# sx1509-breakout_mount_remap2.net
KiCad netlist of a schematic drawn in EAGLE
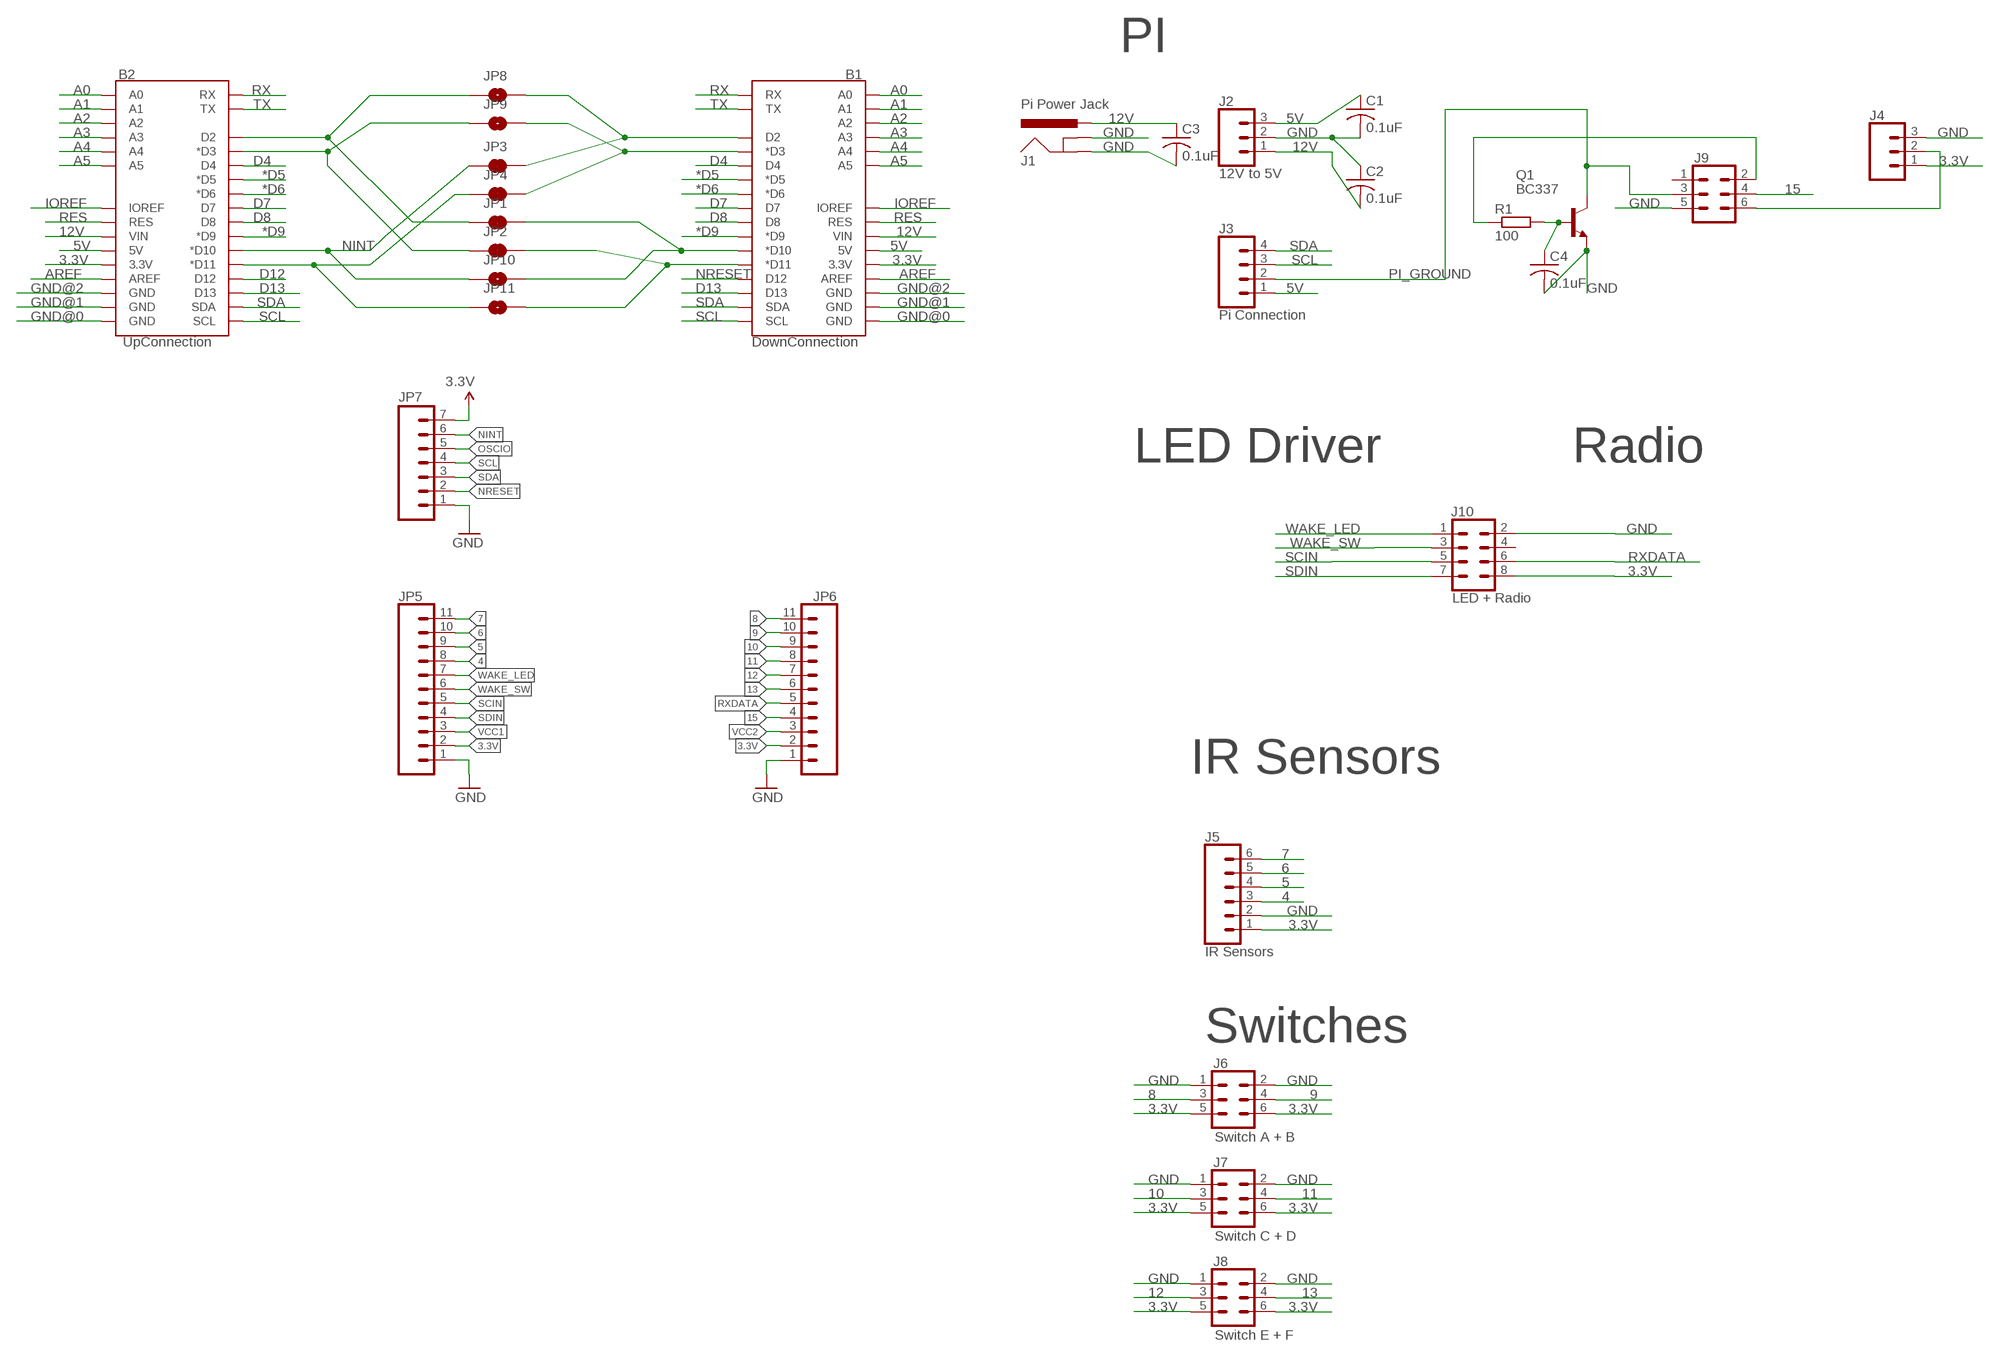
[diagram p0: schematic, sheet 1]

(export (version "E")
  (design (tool "Eeschema 10.0.6"))
  (components
    (comp (ref "B1")
      (value "DownConnection")
      (footprint "eagle-import:UNO_R3_SHIELD_NOLABELS")
      (libsource (lib "eagle-import") (part "ARDUINO_UNO_R3_SHIELDNOLABELS"))
    )
    (comp (ref "B2")
      (value "UpConnection")
      (footprint "eagle-import:UNO_R3_SHIELD_NOLABELS")
      (libsource (lib "eagle-import") (part "ARDUINO_UNO_R3_SHIELDNOLABELS"))
    )
    (comp (ref "C1")
      (value "0.1uF")
      (footprint "eagle-import:C025-024X044")
      (libsource (lib "eagle-import") (part "C-US025-024X044"))
    )
    (comp (ref "C2")
      (value "0.1uF")
      (footprint "eagle-import:C025-024X044")
      (libsource (lib "eagle-import") (part "C-US025-024X044"))
    )
    (comp (ref "C3")
      (value "0.1uF")
      (footprint "eagle-import:C025-024X044")
      (libsource (lib "eagle-import") (part "C-US025-024X044"))
    )
    (comp (ref "C4")
      (value "0.1uF")
      (footprint "eagle-import:C025-024X044")
      (libsource (lib "eagle-import") (part "C-US025-024X044"))
    )
    (comp (ref "J1")
      (value "Pi Power Jack")
      (footprint "eagle-import:POWER_JACK_PTH_BREAD")
      (libsource (lib "eagle-import") (part "POWER_JACKPTH_BREAD"))
    )
    (comp (ref "J2")
      (value "12V to 5V")
      (footprint "eagle-import:1X03")
      (libsource (lib "eagle-import") (part "CONN_03"))
    )
    (comp (ref "J3")
      (value "Pi Connection")
      (footprint "eagle-import:1X04")
      (libsource (lib "eagle-import") (part "CONN_04"))
    )
    (comp (ref "J4")
      (value "CONN_03")
      (footprint "eagle-import:1X03")
      (libsource (lib "eagle-import") (part "CONN_03"))
    )
    (comp (ref "J5")
      (value "IR Sensors")
      (footprint "eagle-import:1X06")
      (libsource (lib "eagle-import") (part "CONN_06SILK_FEMALE_PTH"))
    )
    (comp (ref "J6")
      (value "Switch A + B")
      (footprint "eagle-import:2X3")
      (libsource (lib "eagle-import") (part "CONN_03X2FEMALE"))
    )
    (comp (ref "J7")
      (value "Switch C + D")
      (footprint "eagle-import:2X3")
      (libsource (lib "eagle-import") (part "CONN_03X2FEMALE"))
    )
    (comp (ref "J8")
      (value "Switch E + F")
      (footprint "eagle-import:2X3")
      (libsource (lib "eagle-import") (part "CONN_03X2FEMALE"))
    )
    (comp (ref "J9")
      (value "CONN_03X2NO_SILK")
      (footprint "eagle-import:2X3-NS")
      (libsource (lib "eagle-import") (part "CONN_03X2NO_SILK"))
    )
    (comp (ref "J10")
      (value "LED + Radio")
      (footprint "eagle-import:2X4")
      (libsource (lib "eagle-import") (part "CONN_04X2"))
    )
    (comp (ref "JP1")
      (value "JUMPER-SMT_2_NC_TRACE_NO-SILK")
      (footprint "eagle-import:SMT-JUMPER_2_NC_TRACE_NO-SILK")
      (libsource (lib "eagle-import") (part "JUMPER-SMT_2_NC_TRACE_NO-SILK"))
    )
    (comp (ref "JP2")
      (value "JUMPER-SMT_2_NC_TRACE_NO-SILK")
      (footprint "eagle-import:SMT-JUMPER_2_NC_TRACE_NO-SILK")
      (libsource (lib "eagle-import") (part "JUMPER-SMT_2_NC_TRACE_NO-SILK"))
    )
    (comp (ref "JP3")
      (value "JUMPER-SMT_2_NC_TRACE_NO-SILK")
      (footprint "eagle-import:SMT-JUMPER_2_NC_TRACE_NO-SILK")
      (libsource (lib "eagle-import") (part "JUMPER-SMT_2_NC_TRACE_NO-SILK"))
    )
    (comp (ref "JP4")
      (value "JUMPER-SMT_2_NC_TRACE_NO-SILK")
      (footprint "eagle-import:SMT-JUMPER_2_NC_TRACE_NO-SILK")
      (libsource (lib "eagle-import") (part "JUMPER-SMT_2_NC_TRACE_NO-SILK"))
    )
    (comp (ref "JP5")
      (value "CONN_11")
      (footprint "eagle-import:1X11")
      (libsource (lib "eagle-import") (part "CONN_11"))
    )
    (comp (ref "JP6")
      (value "CONN_11")
      (footprint "eagle-import:1X11")
      (libsource (lib "eagle-import") (part "CONN_11"))
    )
    (comp (ref "JP7")
      (value "M07")
      (footprint "eagle-import:1X07")
      (libsource (lib "eagle-import") (part "M07"))
    )
    (comp (ref "JP8")
      (value "JUMPER-SMT_2_NO_NO-SILK")
      (footprint "eagle-import:SMT-JUMPER_2_NO_NO-SILK")
      (libsource (lib "eagle-import") (part "JUMPER-SMT_2_NO_NO-SILK"))
    )
    (comp (ref "JP9")
      (value "JUMPER-SMT_2_NO_NO-SILK")
      (footprint "eagle-import:SMT-JUMPER_2_NO_NO-SILK")
      (libsource (lib "eagle-import") (part "JUMPER-SMT_2_NO_NO-SILK"))
    )
    (comp (ref "JP10")
      (value "JUMPER-SMT_2_NO_NO-SILK")
      (footprint "eagle-import:SMT-JUMPER_2_NO_NO-SILK")
      (libsource (lib "eagle-import") (part "JUMPER-SMT_2_NO_NO-SILK"))
    )
    (comp (ref "JP11")
      (value "JUMPER-SMT_2_NO_NO-SILK")
      (footprint "eagle-import:SMT-JUMPER_2_NO_NO-SILK")
      (libsource (lib "eagle-import") (part "JUMPER-SMT_2_NO_NO-SILK"))
    )
    (comp (ref "Q1")
      (value "BC337")
      (footprint "eagle-import:TO92")
      (libsource (lib "eagle-import") (part "BC337"))
    )
    (comp (ref "R1")
      (value "100")
      (footprint "eagle-import:0204_7")
      (libsource (lib "eagle-import") (part "R0204/7"))
    )
  )
  (nets
    (net (code "1") (name "/*D5") (class "Default")
      (node (ref "B1") (pin "D5") (pinfunction "*D5_D5") (pintype "bidirectional"))
      (node (ref "B2") (pin "D5") (pinfunction "*D5_D5") (pintype "bidirectional"))
    )
    (net (code "2") (name "/*D6") (class "Default")
      (node (ref "B1") (pin "D6") (pinfunction "*D6_D6") (pintype "bidirectional"))
      (node (ref "B2") (pin "D6") (pinfunction "*D6_D6") (pintype "bidirectional"))
    )
    (net (code "3") (name "/*D9") (class "Default")
      (node (ref "B1") (pin "D9") (pinfunction "*D9_D9") (pintype "bidirectional"))
      (node (ref "B2") (pin "D9") (pinfunction "*D9_D9") (pintype "bidirectional"))
    )
    (net (code "4") (name "/5V") (class "Default")
      (node (ref "B1") (pin "5V") (pinfunction "5V_5V") (pintype "bidirectional"))
      (node (ref "B2") (pin "5V") (pinfunction "5V_5V") (pintype "bidirectional"))
      (node (ref "C1") (pin "1") (pinfunction "1_1") (pintype "passive"))
      (node (ref "J2") (pin "3") (pinfunction "3_3") (pintype "passive"))
      (node (ref "J3") (pin "1") (pinfunction "1_1") (pintype "passive"))
    )
    (net (code "5") (name "/12V") (class "Default")
      (node (ref "B1") (pin "VIN") (pinfunction "VIN_VIN") (pintype "bidirectional"))
      (node (ref "B2") (pin "VIN") (pinfunction "VIN_VIN") (pintype "bidirectional"))
      (node (ref "C2") (pin "2") (pinfunction "2_2") (pintype "passive"))
      (node (ref "C3") (pin "1") (pinfunction "1_1") (pintype "passive"))
      (node (ref "J1") (pin "PWR") (pinfunction "PWR_PWR") (pintype "bidirectional"))
      (node (ref "J2") (pin "1") (pinfunction "1_1") (pintype "passive"))
    )
    (net (code "6") (name "/A0") (class "Default")
      (node (ref "B1") (pin "A0") (pinfunction "A0_A0") (pintype "bidirectional"))
      (node (ref "B2") (pin "A0") (pinfunction "A0_A0") (pintype "bidirectional"))
    )
    (net (code "7") (name "/A1") (class "Default")
      (node (ref "B1") (pin "A1") (pinfunction "A1_A1") (pintype "bidirectional"))
      (node (ref "B2") (pin "A1") (pinfunction "A1_A1") (pintype "bidirectional"))
    )
    (net (code "8") (name "/A2") (class "Default")
      (node (ref "B1") (pin "A2") (pinfunction "A2_A2") (pintype "bidirectional"))
      (node (ref "B2") (pin "A2") (pinfunction "A2_A2") (pintype "bidirectional"))
    )
    (net (code "9") (name "/A3") (class "Default")
      (node (ref "B1") (pin "A3") (pinfunction "A3_A3") (pintype "bidirectional"))
      (node (ref "B2") (pin "A3") (pinfunction "A3_A3") (pintype "bidirectional"))
    )
    (net (code "10") (name "/A4") (class "Default")
      (node (ref "B1") (pin "A4") (pinfunction "A4_A4") (pintype "bidirectional"))
      (node (ref "B2") (pin "A4") (pinfunction "A4_A4") (pintype "bidirectional"))
    )
    (net (code "11") (name "/A5") (class "Default")
      (node (ref "B1") (pin "A5") (pinfunction "A5_A5") (pintype "bidirectional"))
      (node (ref "B2") (pin "A5") (pinfunction "A5_A5") (pintype "bidirectional"))
    )
    (net (code "12") (name "/AREF") (class "Default")
      (node (ref "B1") (pin "AREF") (pinfunction "AREF_AREF") (pintype "bidirectional"))
      (node (ref "B2") (pin "AREF") (pinfunction "AREF_AREF") (pintype "bidirectional"))
    )
    (net (code "13") (name "/D4") (class "Default")
      (node (ref "B1") (pin "D4") (pinfunction "D4_D4") (pintype "bidirectional"))
      (node (ref "B2") (pin "D4") (pinfunction "D4_D4") (pintype "bidirectional"))
    )
    (net (code "14") (name "/D7") (class "Default")
      (node (ref "B1") (pin "D7") (pinfunction "D7_D7") (pintype "bidirectional"))
      (node (ref "B2") (pin "D7") (pinfunction "D7_D7") (pintype "bidirectional"))
    )
    (net (code "15") (name "/D8") (class "Default")
      (node (ref "B1") (pin "D8") (pinfunction "D8_D8") (pintype "bidirectional"))
      (node (ref "B2") (pin "D8") (pinfunction "D8_D8") (pintype "bidirectional"))
    )
    (net (code "16") (name "/D12") (class "Default")
      (node (ref "B2") (pin "D12") (pinfunction "D12_D12") (pintype "bidirectional"))
    )
    (net (code "17") (name "/D13") (class "Default")
      (node (ref "B1") (pin "D13") (pinfunction "D13_D13") (pintype "bidirectional"))
      (node (ref "B2") (pin "D13") (pinfunction "D13_D13") (pintype "bidirectional"))
    )
    (net (code "18") (name "/GND@0") (class "Default")
      (node (ref "B1") (pin "GND@0") (pinfunction "GND_GND@0") (pintype "bidirectional"))
      (node (ref "B2") (pin "GND@0") (pinfunction "GND_GND@0") (pintype "bidirectional"))
    )
    (net (code "19") (name "/GND@1") (class "Default")
      (node (ref "B1") (pin "GND@1") (pinfunction "GND_GND@1") (pintype "bidirectional"))
      (node (ref "B2") (pin "GND@1") (pinfunction "GND_GND@1") (pintype "bidirectional"))
    )
    (net (code "20") (name "/GND@2") (class "Default")
      (node (ref "B1") (pin "GND@2") (pinfunction "GND_GND@2") (pintype "bidirectional"))
      (node (ref "B2") (pin "GND@2") (pinfunction "GND_GND@2") (pintype "bidirectional"))
    )
    (net (code "21") (name "/IOREF") (class "Default")
      (node (ref "B1") (pin "IOREF") (pinfunction "IOREF_IOREF") (pintype "bidirectional"))
      (node (ref "B2") (pin "IOREF") (pinfunction "IOREF_IOREF") (pintype "bidirectional"))
    )
    (net (code "22") (name "/PI_GROUND") (class "Default")
      (node (ref "J3") (pin "2") (pinfunction "2_2") (pintype "passive"))
      (node (ref "J9") (pin "3") (pinfunction "3_3") (pintype "bidirectional"))
      (node (ref "Q1") (pin "3") (pinfunction "C_3") (pintype "passive"))
    )
    (net (code "23") (name "/RES") (class "Default")
      (node (ref "B1") (pin "RES") (pinfunction "RES_RES") (pintype "bidirectional"))
      (node (ref "B2") (pin "RES") (pinfunction "RES_RES") (pintype "bidirectional"))
    )
    (net (code "24") (name "/RX") (class "Default")
      (node (ref "B1") (pin "RX") (pinfunction "RX_RX") (pintype "bidirectional"))
      (node (ref "B2") (pin "RX") (pinfunction "RX_RX") (pintype "bidirectional"))
    )
    (net (code "25") (name "/TX") (class "Default")
      (node (ref "B1") (pin "TX") (pinfunction "TX_TX") (pintype "bidirectional"))
      (node (ref "B2") (pin "TX") (pinfunction "TX_TX") (pintype "bidirectional"))
    )
    (net (code "26") (name "3.3V") (class "Default")
      (node (ref "B1") (pin "3.3V") (pinfunction "3.3V_3.3V") (pintype "bidirectional"))
      (node (ref "B2") (pin "3.3V") (pinfunction "3.3V_3.3V") (pintype "bidirectional"))
      (node (ref "J10") (pin "8") (pinfunction "8_8") (pintype "passive"))
      (node (ref "J4") (pin "1") (pinfunction "1_1") (pintype "passive"))
      (node (ref "J5") (pin "1") (pinfunction "1_1") (pintype "passive"))
      (node (ref "J6") (pin "5") (pinfunction "5_5") (pintype "bidirectional"))
      (node (ref "J6") (pin "6") (pinfunction "6_6") (pintype "bidirectional"))
      (node (ref "J7") (pin "5") (pinfunction "5_5") (pintype "bidirectional"))
      (node (ref "J7") (pin "6") (pinfunction "6_6") (pintype "bidirectional"))
      (node (ref "J8") (pin "5") (pinfunction "5_5") (pintype "bidirectional"))
      (node (ref "J8") (pin "6") (pinfunction "6_6") (pintype "bidirectional"))
      (node (ref "JP5") (pin "2") (pinfunction "2_2") (pintype "passive"))
      (node (ref "JP6") (pin "2") (pinfunction "2_2") (pintype "passive"))
      (node (ref "JP7") (pin "7") (pinfunction "7_7") (pintype "passive"))
    )
    (net (code "27") (name "4") (class "Default")
      (node (ref "J5") (pin "3") (pinfunction "3_3") (pintype "passive"))
      (node (ref "JP5") (pin "8") (pinfunction "8_8") (pintype "passive"))
    )
    (net (code "28") (name "5") (class "Default")
      (node (ref "J5") (pin "4") (pinfunction "4_4") (pintype "passive"))
      (node (ref "JP5") (pin "9") (pinfunction "9_9") (pintype "passive"))
    )
    (net (code "29") (name "6") (class "Default")
      (node (ref "J5") (pin "5") (pinfunction "5_5") (pintype "passive"))
      (node (ref "JP5") (pin "10") (pinfunction "10_10") (pintype "passive"))
    )
    (net (code "30") (name "7") (class "Default")
      (node (ref "J5") (pin "6") (pinfunction "6_6") (pintype "passive"))
      (node (ref "JP5") (pin "11") (pinfunction "11_11") (pintype "passive"))
    )
    (net (code "31") (name "8") (class "Default")
      (node (ref "J6") (pin "3") (pinfunction "3_3") (pintype "bidirectional"))
      (node (ref "JP6") (pin "11") (pinfunction "11_11") (pintype "passive"))
    )
    (net (code "32") (name "9") (class "Default")
      (node (ref "J6") (pin "4") (pinfunction "4_4") (pintype "bidirectional"))
      (node (ref "JP6") (pin "10") (pinfunction "10_10") (pintype "passive"))
    )
    (net (code "33") (name "10") (class "Default")
      (node (ref "J7") (pin "3") (pinfunction "3_3") (pintype "bidirectional"))
      (node (ref "JP6") (pin "9") (pinfunction "9_9") (pintype "passive"))
    )
    (net (code "34") (name "11") (class "Default")
      (node (ref "J7") (pin "4") (pinfunction "4_4") (pintype "bidirectional"))
      (node (ref "JP6") (pin "8") (pinfunction "8_8") (pintype "passive"))
    )
    (net (code "35") (name "12") (class "Default")
      (node (ref "J8") (pin "3") (pinfunction "3_3") (pintype "bidirectional"))
      (node (ref "JP6") (pin "7") (pinfunction "7_7") (pintype "passive"))
    )
    (net (code "36") (name "13") (class "Default")
      (node (ref "J8") (pin "4") (pinfunction "4_4") (pintype "bidirectional"))
      (node (ref "JP6") (pin "6") (pinfunction "6_6") (pintype "passive"))
    )
    (net (code "37") (name "15") (class "Default")
      (node (ref "J9") (pin "4") (pinfunction "4_4") (pintype "bidirectional"))
      (node (ref "JP6") (pin "4") (pinfunction "4_4") (pintype "passive"))
    )
    (net (code "38") (name "GND") (class "Default")
      (node (ref "C1") (pin "2") (pinfunction "2_2") (pintype "passive"))
      (node (ref "C2") (pin "1") (pinfunction "1_1") (pintype "passive"))
      (node (ref "C3") (pin "2") (pinfunction "2_2") (pintype "passive"))
      (node (ref "C4") (pin "2") (pinfunction "2_2") (pintype "passive"))
      (node (ref "J1") (pin "GND") (pinfunction "GND_GND") (pintype "bidirectional"))
      (node (ref "J1") (pin "GNDBREAK") (pinfunction "GNDBREAK_GNDBREAK") (pintype "bidirectional"))
      (node (ref "J10") (pin "2") (pinfunction "2_2") (pintype "passive"))
      (node (ref "J2") (pin "2") (pinfunction "2_2") (pintype "passive"))
      (node (ref "J4") (pin "3") (pinfunction "3_3") (pintype "passive"))
      (node (ref "J5") (pin "2") (pinfunction "2_2") (pintype "passive"))
      (node (ref "J6") (pin "1") (pinfunction "1_1") (pintype "bidirectional"))
      (node (ref "J6") (pin "2") (pinfunction "2_2") (pintype "bidirectional"))
      (node (ref "J7") (pin "1") (pinfunction "1_1") (pintype "bidirectional"))
      (node (ref "J7") (pin "2") (pinfunction "2_2") (pintype "bidirectional"))
      (node (ref "J8") (pin "1") (pinfunction "1_1") (pintype "bidirectional"))
      (node (ref "J8") (pin "2") (pinfunction "2_2") (pintype "bidirectional"))
      (node (ref "J9") (pin "5") (pinfunction "5_5") (pintype "bidirectional"))
      (node (ref "JP5") (pin "1") (pinfunction "1_1") (pintype "passive"))
      (node (ref "JP6") (pin "1") (pinfunction "1_1") (pintype "passive"))
      (node (ref "JP7") (pin "1") (pinfunction "1_1") (pintype "passive"))
      (node (ref "Q1") (pin "1") (pinfunction "E_1") (pintype "passive"))
    )
    (net (code "39") (name "NINT") (class "Default")
      (node (ref "B2") (pin "D10") (pinfunction "*D10_D10") (pintype "bidirectional"))
      (node (ref "JP10") (pin "1") (pinfunction "1_1") (pintype "passive"))
      (node (ref "JP3") (pin "1") (pinfunction "1_1") (pintype "passive"))
      (node (ref "JP7") (pin "6") (pinfunction "6_6") (pintype "passive"))
    )
    (net (code "40") (name "NRESET") (class "Default")
      (node (ref "B1") (pin "D12") (pinfunction "D12_D12") (pintype "bidirectional"))
      (node (ref "JP7") (pin "2") (pinfunction "2_2") (pintype "passive"))
    )
    (net (code "41") (name "Net-(B1-*D3)") (class "Default")
      (node (ref "B1") (pin "D3") (pinfunction "*D3_D3") (pintype "bidirectional"))
      (node (ref "JP4") (pin "2") (pinfunction "2_2") (pintype "passive"))
      (node (ref "JP9") (pin "2") (pinfunction "2_2") (pintype "passive"))
    )
    (net (code "42") (name "Net-(B1-*D10)") (class "Default")
      (node (ref "B1") (pin "D10") (pinfunction "*D10_D10") (pintype "bidirectional"))
      (node (ref "JP1") (pin "2") (pinfunction "2_2") (pintype "passive"))
      (node (ref "JP10") (pin "2") (pinfunction "2_2") (pintype "passive"))
    )
    (net (code "43") (name "Net-(B1-*D11)") (class "Default")
      (node (ref "B1") (pin "D11") (pinfunction "*D11_D11") (pintype "bidirectional"))
      (node (ref "JP11") (pin "2") (pinfunction "2_2") (pintype "passive"))
      (node (ref "JP2") (pin "2") (pinfunction "2_2") (pintype "passive"))
    )
    (net (code "44") (name "Net-(B1-PadD2)") (class "Default")
      (node (ref "B1") (pin "D2") (pinfunction "D2_D2") (pintype "bidirectional"))
      (node (ref "JP3") (pin "2") (pinfunction "2_2") (pintype "passive"))
      (node (ref "JP8") (pin "2") (pinfunction "2_2") (pintype "passive"))
    )
    (net (code "45") (name "Net-(B2-*D3)") (class "Default")
      (node (ref "B2") (pin "D3") (pinfunction "*D3_D3") (pintype "bidirectional"))
      (node (ref "JP2") (pin "1") (pinfunction "1_1") (pintype "passive"))
      (node (ref "JP9") (pin "1") (pinfunction "1_1") (pintype "passive"))
    )
    (net (code "46") (name "Net-(B2-*D11)") (class "Default")
      (node (ref "B2") (pin "D11") (pinfunction "*D11_D11") (pintype "bidirectional"))
      (node (ref "JP11") (pin "1") (pinfunction "1_1") (pintype "passive"))
      (node (ref "JP4") (pin "1") (pinfunction "1_1") (pintype "passive"))
    )
    (net (code "47") (name "Net-(B2-PadD2)") (class "Default")
      (node (ref "B2") (pin "D2") (pinfunction "D2_D2") (pintype "bidirectional"))
      (node (ref "JP1") (pin "1") (pinfunction "1_1") (pintype "passive"))
      (node (ref "JP8") (pin "1") (pinfunction "1_1") (pintype "passive"))
    )
    (net (code "48") (name "Net-(J4-Pad2)") (class "Default")
      (node (ref "J4") (pin "2") (pinfunction "2_2") (pintype "passive"))
      (node (ref "J9") (pin "6") (pinfunction "6_6") (pintype "bidirectional"))
    )
    (net (code "49") (name "Net-(J9-Pad2)") (class "Default")
      (node (ref "J9") (pin "2") (pinfunction "2_2") (pintype "bidirectional"))
      (node (ref "R1") (pin "1") (pinfunction "1_1") (pintype "passive"))
    )
    (net (code "50") (name "Net-(Q1-B)") (class "Default")
      (node (ref "C4") (pin "1") (pinfunction "1_1") (pintype "passive"))
      (node (ref "Q1") (pin "2") (pinfunction "B_2") (pintype "passive"))
      (node (ref "R1") (pin "2") (pinfunction "2_2") (pintype "passive"))
    )
    (net (code "51") (name "OSCIO") (class "Default")
      (node (ref "JP7") (pin "5") (pinfunction "5_5") (pintype "passive"))
    )
    (net (code "52") (name "RXDATA") (class "Default")
      (node (ref "J10") (pin "6") (pinfunction "6_6") (pintype "passive"))
      (node (ref "JP6") (pin "5") (pinfunction "5_5") (pintype "passive"))
    )
    (net (code "53") (name "SCIN") (class "Default")
      (node (ref "J10") (pin "5") (pinfunction "5_5") (pintype "passive"))
      (node (ref "JP5") (pin "5") (pinfunction "5_5") (pintype "passive"))
    )
    (net (code "54") (name "SCL") (class "Default")
      (node (ref "B1") (pin "SCL") (pinfunction "SCL_SCL") (pintype "bidirectional"))
      (node (ref "B2") (pin "SCL") (pinfunction "SCL_SCL") (pintype "bidirectional"))
      (node (ref "J3") (pin "3") (pinfunction "3_3") (pintype "passive"))
      (node (ref "JP7") (pin "4") (pinfunction "4_4") (pintype "passive"))
    )
    (net (code "55") (name "SDA") (class "Default")
      (node (ref "B1") (pin "SDA") (pinfunction "SDA_SDA") (pintype "bidirectional"))
      (node (ref "B2") (pin "SDA") (pinfunction "SDA_SDA") (pintype "bidirectional"))
      (node (ref "J3") (pin "4") (pinfunction "4_4") (pintype "passive"))
      (node (ref "JP7") (pin "3") (pinfunction "3_3") (pintype "passive"))
    )
    (net (code "56") (name "SDIN") (class "Default")
      (node (ref "J10") (pin "7") (pinfunction "7_7") (pintype "passive"))
      (node (ref "JP5") (pin "4") (pinfunction "4_4") (pintype "passive"))
    )
    (net (code "57") (name "VCC1") (class "Default")
      (node (ref "JP5") (pin "3") (pinfunction "3_3") (pintype "passive"))
    )
    (net (code "58") (name "VCC2") (class "Default")
      (node (ref "JP6") (pin "3") (pinfunction "3_3") (pintype "passive"))
    )
    (net (code "59") (name "WAKE_LED") (class "Default")
      (node (ref "J10") (pin "1") (pinfunction "1_1") (pintype "passive"))
      (node (ref "JP5") (pin "7") (pinfunction "7_7") (pintype "passive"))
    )
    (net (code "60") (name "WAKE_SW") (class "Default")
      (node (ref "J10") (pin "3") (pinfunction "3_3") (pintype "passive"))
      (node (ref "JP5") (pin "6") (pinfunction "6_6") (pintype "passive"))
    )
    (net (code "61") (name "unconnected-(J9-Pad1)") (class "Default")
      (node (ref "J9") (pin "1") (pinfunction "1_1") (pintype "bidirectional"))
    )
    (net (code "62") (name "unconnected-(J10-Pad4)") (class "Default")
      (node (ref "J10") (pin "4") (pinfunction "4_4") (pintype "passive"))
    )
  )
)
